# ProPrj___2024-09-12.net
KiCad netlist of a schematic drawn in EasyEDA Pro
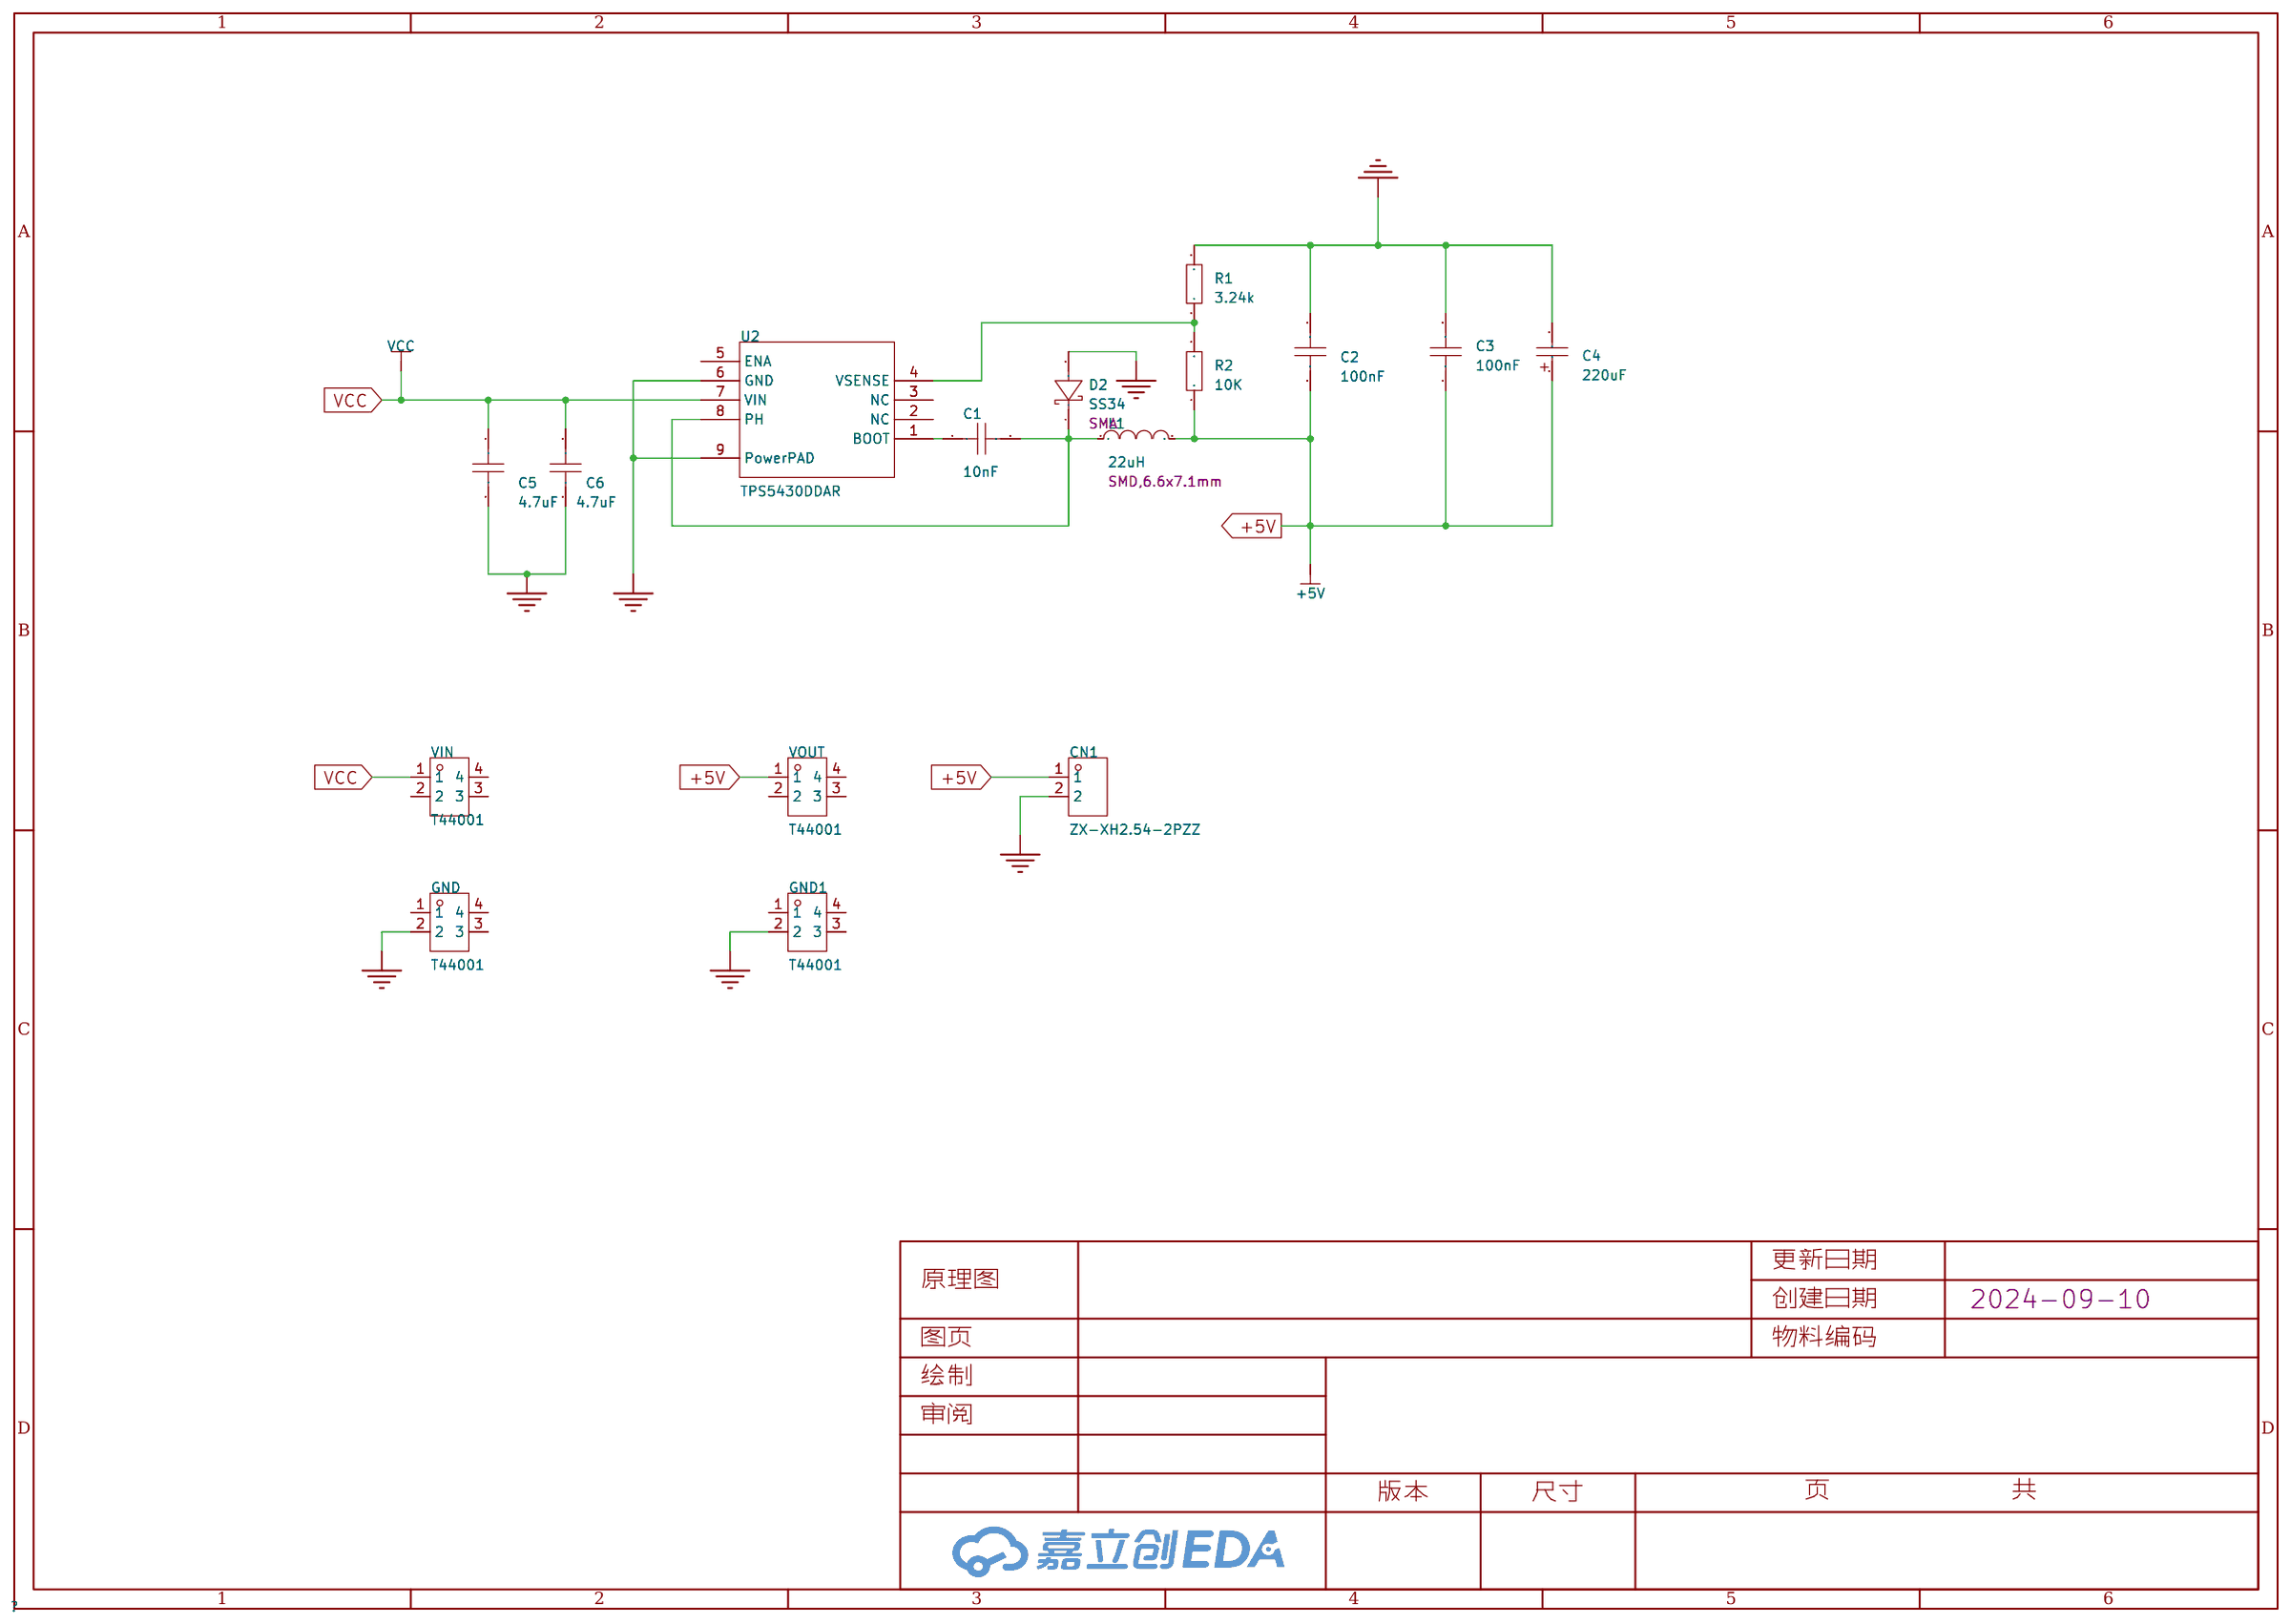
[diagram p0: schematic sheet]

(export (version "E")
  (design (tool "Eeschema 10.0.6"))
  (components
    (comp (ref "C1")
      (value "10nF")
      (footprint "easyedapro:C0603")
      (libsource (lib "easyedapro") (part "CapAcitance"))
    )
    (comp (ref "C2")
      (value "100nF")
      (footprint "easyedapro:C0603")
      (libsource (lib "easyedapro") (part "CapAcitance"))
    )
    (comp (ref "C3")
      (value "100nF")
      (footprint "easyedapro:C0603")
      (libsource (lib "easyedapro") (part "CapAcitance"))
    )
    (comp (ref "C4")
      (value "220uF")
      (footprint "easyedapro:C_Ele_SMD_3x5.4mm")
      (libsource (lib "easyedapro") (part "CAP"))
    )
    (comp (ref "C5")
      (value "4.7uF")
      (footprint "easyedapro:C0603")
      (libsource (lib "easyedapro") (part "CapAcitance"))
    )
    (comp (ref "C6")
      (value "4.7uF")
      (footprint "easyedapro:C0603")
      (libsource (lib "easyedapro") (part "CapAcitance"))
    )
    (comp (ref "CN1")
      (value "ZX-XH2.54-2PZZ")
      (footprint "easyedapro:CONN-TH_2P-P2.50_HX25003-2A")
      (fields (field (name "Manufacturer") "Megastar(兆星)"))
      (libsource (lib "easyedapro") (part "ZX-XH2.54-2PZZ"))
    )
    (comp (ref "D2")
      (value "SS34")
      (footprint "easyedapro:SMA_L4.3-W2.7-LS5.0-RD")
      (description "二极管配置:独立式;正向压降(Vf):550mV@3A;直流反向耐压(Vr):40V;整流电流:3A;")
      (fields (field (name "Manufacturer") "MDD(辰达半导体)") (field (name "Supplier Footprint") "SMA"))
      (libsource (lib "easyedapro") (part "SS34_C9900017801"))
    )
    (comp (ref "GND")
      (value "T44001")
      (footprint "easyedapro:CONN-TH_T44001")
      (fields (field (name "Manufacturer") "XFCN(兴飞)"))
      (libsource (lib "easyedapro") (part "T44001"))
    )
    (comp (ref "GND1")
      (value "T44001")
      (footprint "easyedapro:CONN-TH_T44001")
      (fields (field (name "Manufacturer") "XFCN(兴飞)"))
      (libsource (lib "easyedapro") (part "T44001"))
    )
    (comp (ref "L1")
      (value "22uH")
      (footprint "easyedapro:IND-SMD_L7.1-W6.6")
      (description "电感值:22uH;精度:±20%;额定电流:3A;")
      (fields
        (field (name "Manufacturer Part") "YSPI0630A-220M")
        (field (name "Manufacturer") "YJYCOIN(益嘉源)")
        (field (name "Supplier Footprint") "SMD,6.6x7.1mm")
      )
      (libsource (lib "easyedapro") (part "YSPI0630A-220M"))
    )
    (comp (ref "R1")
      (value "3.24k")
      (footprint "easyedapro:R0603")
      (libsource (lib "easyedapro") (part "电阻"))
    )
    (comp (ref "R2") (value "10K") (footprint "easyedapro:R0603") (libsource (lib "easyedapro") (part "电阻")))
    (comp (ref "U2")
      (value "TPS5430DDAR")
      (footprint "easyedapro:ESOP-8_L4.9-W3.9-P1.27-LS6.0-TL-EP")
      (description "功能类型:降压型;输出类型:可调;输入电压:5.5V~36V;输出电压:1.221V~32.04V;输出电流(最大值):3A;")
      (fields (field (name "Manufacturer") "TI(德州仪器)"))
      (libsource (lib "easyedapro") (part "TPS5430DDAR"))
    )
    (comp (ref "VIN")
      (value "T44001")
      (footprint "easyedapro:CONN-TH_T44001")
      (fields (field (name "Manufacturer") "XFCN(兴飞)"))
      (libsource (lib "easyedapro") (part "T44001"))
    )
    (comp (ref "VOUT")
      (value "T44001")
      (footprint "easyedapro:CONN-TH_T44001")
      (fields (field (name "Manufacturer") "XFCN(兴飞)"))
      (libsource (lib "easyedapro") (part "T44001"))
    )
  )
  (nets
    (net (code "1") (name "+5V") (class "Default")
      (node (ref "C2") (pin "2") (pinfunction "2_2") (pintype "input"))
      (node (ref "C3") (pin "1") (pinfunction "1_1") (pintype "input"))
      (node (ref "C4") (pin "1") (pinfunction "1_1") (pintype "input"))
      (node (ref "CN1") (pin "1") (pinfunction "1_1") (pintype "unspecified"))
      (node (ref "L1") (pin "2") (pinfunction "2_2") (pintype "unspecified"))
      (node (ref "R2") (pin "1") (pinfunction "1_1") (pintype "input"))
      (node (ref "VOUT") (pin "1") (pinfunction "1_1") (pintype "input"))
    )
    (net (code "2") (name "GND") (class "Default")
      (node (ref "C2") (pin "1") (pinfunction "1_1") (pintype "input"))
      (node (ref "C3") (pin "2") (pinfunction "2_2") (pintype "input"))
      (node (ref "C4") (pin "2") (pinfunction "2_2") (pintype "input"))
      (node (ref "C5") (pin "2") (pinfunction "2_2") (pintype "input"))
      (node (ref "C6") (pin "2") (pinfunction "2_2") (pintype "input"))
      (node (ref "CN1") (pin "2") (pinfunction "2_2") (pintype "unspecified"))
      (node (ref "D2") (pin "2") (pinfunction "K_2") (pintype "unspecified"))
      (node (ref "GND") (pin "2") (pinfunction "2_2") (pintype "input"))
      (node (ref "GND1") (pin "2") (pinfunction "2_2") (pintype "input"))
      (node (ref "R1") (pin "2") (pinfunction "2_2") (pintype "input"))
      (node (ref "U2") (pin "6") (pinfunction "GND_6") (pintype "unspecified"))
      (node (ref "U2") (pin "9") (pinfunction "PowerPAD_9") (pintype "unspecified"))
    )
    (net (code "3") (name "Net-(D2-A)") (class "Default")
      (node (ref "C1") (pin "2") (pinfunction "2_2") (pintype "input"))
      (node (ref "D2") (pin "1") (pinfunction "A_1") (pintype "unspecified"))
      (node (ref "L1") (pin "1") (pinfunction "1_1") (pintype "unspecified"))
      (node (ref "U2") (pin "8") (pinfunction "PH_8") (pintype "unspecified"))
    )
    (net (code "4") (name "Net-(U2-BOOT)") (class "Default")
      (node (ref "C1") (pin "1") (pinfunction "1_1") (pintype "input"))
      (node (ref "U2") (pin "1") (pinfunction "BOOT_1") (pintype "unspecified"))
    )
    (net (code "5") (name "Net-(U2-VSENSE)") (class "Default")
      (node (ref "R1") (pin "1") (pinfunction "1_1") (pintype "input"))
      (node (ref "R2") (pin "2") (pinfunction "2_2") (pintype "input"))
      (node (ref "U2") (pin "4") (pinfunction "VSENSE_4") (pintype "unspecified"))
    )
    (net (code "6") (name "VCC") (class "Default")
      (node (ref "C5") (pin "1") (pinfunction "1_1") (pintype "input"))
      (node (ref "C6") (pin "1") (pinfunction "1_1") (pintype "input"))
      (node (ref "U2") (pin "7") (pinfunction "VIN_7") (pintype "unspecified"))
      (node (ref "VIN") (pin "1") (pinfunction "1_1") (pintype "input"))
    )
    (net (code "7") (name "unconnected-(GND-Pad1)") (class "Default")
      (node (ref "GND") (pin "1") (pinfunction "1_1") (pintype "input"))
    )
    (net (code "8") (name "unconnected-(GND-Pad3)") (class "Default")
      (node (ref "GND") (pin "3") (pinfunction "3_3") (pintype "input"))
    )
    (net (code "9") (name "unconnected-(GND-Pad4)") (class "Default")
      (node (ref "GND") (pin "4") (pinfunction "4_4") (pintype "input"))
    )
    (net (code "10") (name "unconnected-(GND1-Pad1)") (class "Default")
      (node (ref "GND1") (pin "1") (pinfunction "1_1") (pintype "input"))
    )
    (net (code "11") (name "unconnected-(GND1-Pad3)") (class "Default")
      (node (ref "GND1") (pin "3") (pinfunction "3_3") (pintype "input"))
    )
    (net (code "12") (name "unconnected-(GND1-Pad4)") (class "Default")
      (node (ref "GND1") (pin "4") (pinfunction "4_4") (pintype "input"))
    )
    (net (code "13") (name "unconnected-(U2-ENA-Pad5)") (class "Default")
      (node (ref "U2") (pin "5") (pinfunction "ENA_5") (pintype "unspecified"))
    )
    (net (code "14") (name "unconnected-(U2-NC-Pad2)") (class "Default")
      (node (ref "U2") (pin "2") (pinfunction "NC_2") (pintype "unspecified"))
    )
    (net (code "15") (name "unconnected-(U2-NC-Pad3)") (class "Default")
      (node (ref "U2") (pin "3") (pinfunction "NC_3") (pintype "unspecified"))
    )
    (net (code "16") (name "unconnected-(VIN-Pad2)") (class "Default")
      (node (ref "VIN") (pin "2") (pinfunction "2_2") (pintype "input"))
    )
    (net (code "17") (name "unconnected-(VIN-Pad3)") (class "Default")
      (node (ref "VIN") (pin "3") (pinfunction "3_3") (pintype "input"))
    )
    (net (code "18") (name "unconnected-(VIN-Pad4)") (class "Default")
      (node (ref "VIN") (pin "4") (pinfunction "4_4") (pintype "input"))
    )
    (net (code "19") (name "unconnected-(VOUT-Pad2)") (class "Default")
      (node (ref "VOUT") (pin "2") (pinfunction "2_2") (pintype "input"))
    )
    (net (code "20") (name "unconnected-(VOUT-Pad3)") (class "Default")
      (node (ref "VOUT") (pin "3") (pinfunction "3_3") (pintype "input"))
    )
    (net (code "21") (name "unconnected-(VOUT-Pad4)") (class "Default")
      (node (ref "VOUT") (pin "4") (pinfunction "4_4") (pintype "input"))
    )
  )
)
